# CAN_Trcv.net
KiCad netlist of a schematic drawn in Altium Designer
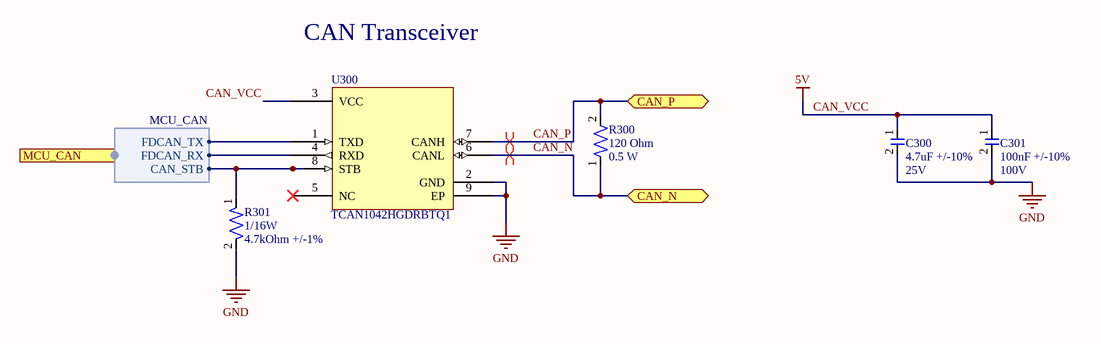
[diagram p0: CAN_Trcv.SchDoc]

(export (version "E")
  (design (tool "Eeschema 10.0.6"))
  (components
    (comp (ref "C300")
      (value "TMK107BBJ475KA-T")
      (footprint "MasterLib:CAP-0603")
      (description "4.7 µF ±10% 25V Ceramic Capacitor X5R 0603 (1608 Metric)")
      (fields
        (field (name "MANUFACTURER") "Taiyo Yuden")
        (field (name "CAPACITANCE") "4.7uF +/-10%")
        (field (name "VOLTAGE RATING") "25V")
      )
      (libsource (lib "MasterLib") (part "CAP-4.7U-0001"))
    )
    (comp (ref "C301")
      (value "CC0603KRX7R0BB104")
      (footprint "MasterLib:CAP-0603")
      (description "CAP CER 0.1UF 100V X7R 0603")
      (fields
        (field (name "MANUFACTURER") "YAGEO")
        (field (name "CAPACITANCE") "100nF +/-10%")
        (field (name "VOLTAGE RATING") "100V")
      )
      (libsource (lib "MasterLib") (part "CAP-100N-0001"))
    )
    (comp (ref "R300")
      (value "CRGH1206F120R")
      (footprint "MasterLib:RES-1206")
      (description "120 Ohms ±1% 0.5W, 1/2W Chip Resistor 1206 (3216 Metric) Thick Film")
      (fields
        (field (name "TOLERANCE") "1%")
        (field (name "RESISTANCE") "120 Ohm")
        (field (name "POWER") "0.5 W")
      )
      (libsource (lib "MasterLib") (part "RES-120-0002"))
    )
    (comp (ref "R301")
      (value "RC0402FR-074K7P")
      (footprint "MasterLib:RES-0402")
      (description "RES SMD 4.7K OHM 1% 1/16W 0402")
      (fields
        (field (name "MANUFACTURER") "YAGEO")
        (field (name "POWER RATING") "1/16W")
        (field (name "RESISTANCE") "4.7kOhm +/-1%")
      )
      (libsource (lib "MasterLib") (part "RES-4.7K-0001"))
    )
    (comp (ref "U300")
      (value "TCAN1042HGDRBTQ1")
      (footprint "MasterLib:IC-8-VSON")
      (description "1/1 Transceiver CANbus 8-VSON (3x3)")
      (fields (field (name "MANUFACTURER") "Texas Instrument"))
      (libsource (lib "MasterLib") (part "IC-CAN-TRANSCEIVER-0002"))
    )
  )
  (nets
    (net (code "2") (name "/CAN_N") (class "Default")
      (node (ref "R300") (pin "1") (pinfunction "1_1") (pintype "passive"))
      (node (ref "U300") (pin "6") (pinfunction "CANL_6") (pintype "bidirectional"))
    )
    (net (code "3") (name "/CAN_P") (class "Default")
      (node (ref "R300") (pin "2") (pinfunction "2_2") (pintype "passive"))
      (node (ref "U300") (pin "7") (pinfunction "CANH_7") (pintype "bidirectional"))
    )
    (net (code "4") (name "/CAN_STB") (class "Default")
      (node (ref "R301") (pin "1") (pinfunction "1_1") (pintype "passive"))
      (node (ref "U300") (pin "8") (pinfunction "STB_8") (pintype "input"))
    )
    (net (code "5") (name "/FDCAN_RX") (class "Default")
      (node (ref "U300") (pin "4") (pinfunction "RXD_4") (pintype "output"))
    )
    (net (code "6") (name "/FDCAN_TX") (class "Default")
      (node (ref "U300") (pin "1") (pinfunction "TXD_1") (pintype "input"))
    )
    (net (code "8") (name "5V") (class "Default")
      (node (ref "C300") (pin "1") (pinfunction "1_1") (pintype "passive"))
      (node (ref "C301") (pin "1") (pinfunction "1_1") (pintype "passive"))
      (node (ref "U300") (pin "3") (pinfunction "VCC_3") (pintype "power_in"))
    )
    (net (code "9") (name "GND") (class "Default")
      (node (ref "C300") (pin "2") (pinfunction "2_2") (pintype "passive"))
      (node (ref "C301") (pin "2") (pinfunction "2_2") (pintype "passive"))
      (node (ref "R301") (pin "2") (pinfunction "2_2") (pintype "passive"))
      (node (ref "U300") (pin "2") (pinfunction "GND_2") (pintype "power_in"))
      (node (ref "U300") (pin "9") (pinfunction "EP_9") (pintype "power_in"))
    )
    (net (code "10") (name "unconnected-(U300-NC-Pad5)") (class "Default")
      (node (ref "U300") (pin "5") (pinfunction "NC_5") (pintype "power_in+no_connect"))
    )
  )
)
